# combined_pressure_sensor_rev0.net
KiCad netlist of a schematic drawn in EAGLE
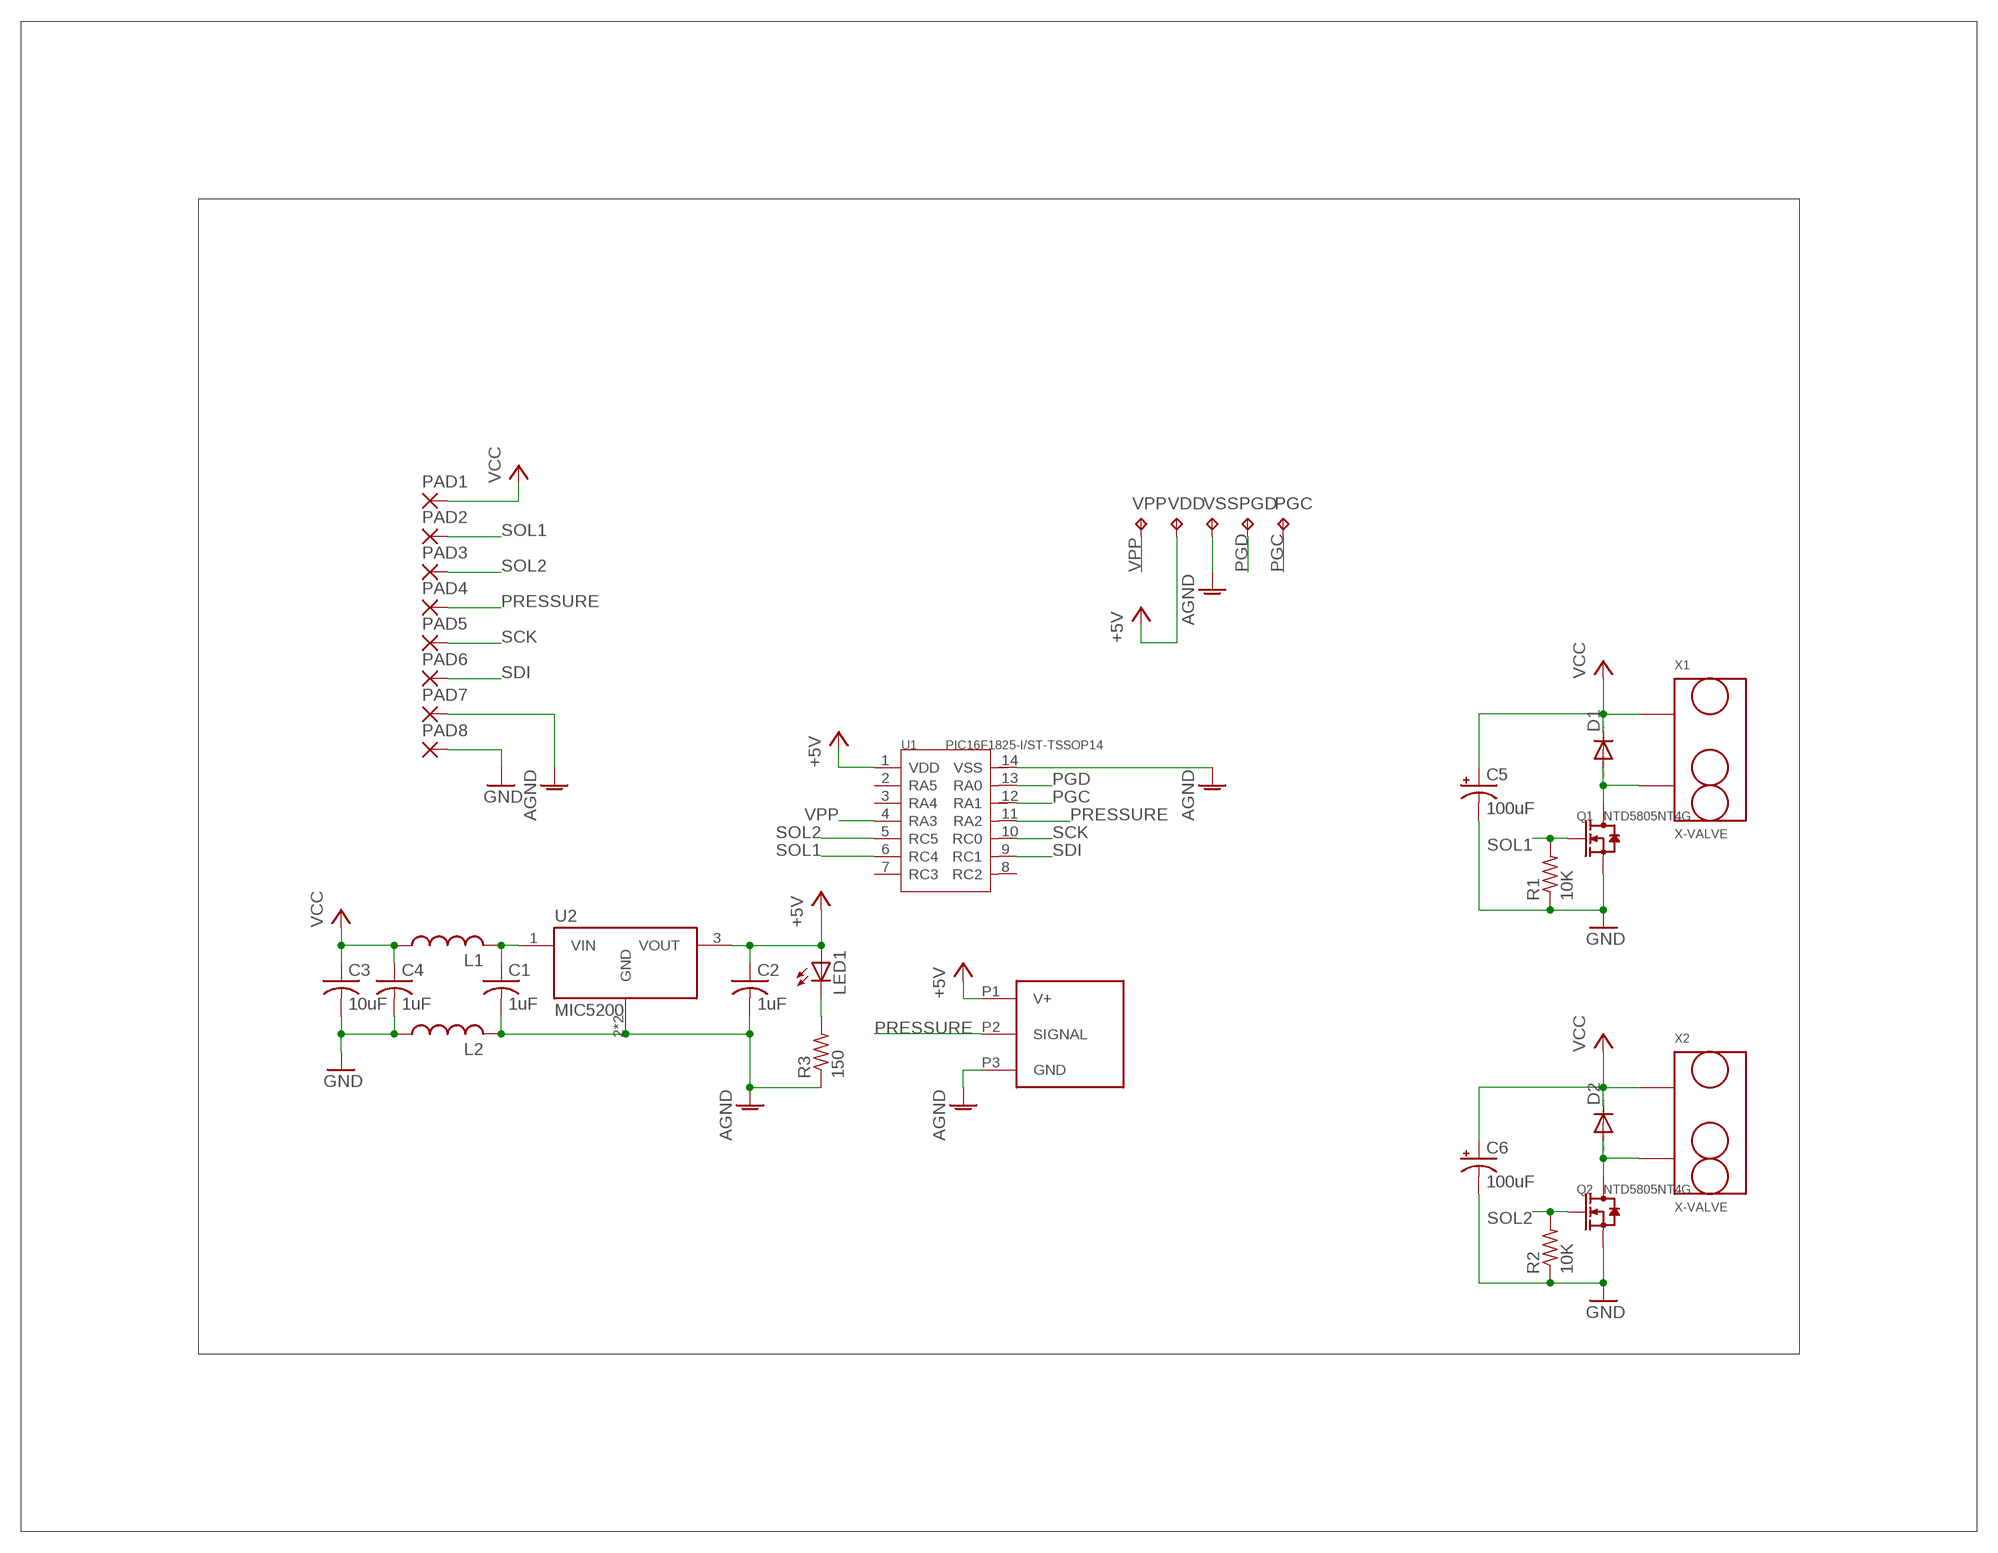
[diagram p0: schematic, sheet 1]

(export (version "E")
  (design (tool "Eeschema 10.0.6"))
  (components
    (comp (ref "C1")
      (value "1uF")
      (footprint "eagle-import:C0603")
      (libsource (lib "eagle-import") (part "C-USC0603"))
    )
    (comp (ref "C2")
      (value "1uF")
      (footprint "eagle-import:C0603")
      (libsource (lib "eagle-import") (part "C-USC0603"))
    )
    (comp (ref "C3")
      (value "10uF")
      (footprint "eagle-import:C1206")
      (libsource (lib "eagle-import") (part "C-USC1206"))
    )
    (comp (ref "C4")
      (value "1uF")
      (footprint "eagle-import:C0603")
      (libsource (lib "eagle-import") (part "C-USC0603"))
    )
    (comp (ref "C5")
      (value "100uF")
      (footprint "eagle-import:153CLV-0605")
      (libsource (lib "eagle-import") (part "CPOL-US153CLV-0605"))
    )
    (comp (ref "C6")
      (value "100uF")
      (footprint "eagle-import:153CLV-0605")
      (libsource (lib "eagle-import") (part "CPOL-US153CLV-0605"))
    )
    (comp (ref "D1")
      (value "DIODE-SOD523")
      (footprint "eagle-import:SOD523")
      (libsource (lib "eagle-import") (part "DIODE-SOD523"))
    )
    (comp (ref "D2")
      (value "DIODE-SOD523")
      (footprint "eagle-import:SOD523")
      (libsource (lib "eagle-import") (part "DIODE-SOD523"))
    )
    (comp (ref "L1")
      (value "L-USL1206")
      (footprint "eagle-import:L1206")
      (libsource (lib "eagle-import") (part "L-USL1206"))
    )
    (comp (ref "L2")
      (value "L-USL1206")
      (footprint "eagle-import:L1206")
      (libsource (lib "eagle-import") (part "L-USL1206"))
    )
    (comp (ref "LED1")
      (value "LEDCHIP-LED0603")
      (footprint "eagle-import:CHIP-LED0603")
      (libsource (lib "eagle-import") (part "LEDCHIP-LED0603"))
    )
    (comp (ref "PAD1")
      (value "SMD2")
      (footprint "eagle-import:SMD1,27-2,54")
      (libsource (lib "eagle-import") (part "SMD2"))
    )
    (comp (ref "PAD2")
      (value "SMD2")
      (footprint "eagle-import:SMD1,27-2,54")
      (libsource (lib "eagle-import") (part "SMD2"))
    )
    (comp (ref "PAD3")
      (value "SMD2")
      (footprint "eagle-import:SMD1,27-2,54")
      (libsource (lib "eagle-import") (part "SMD2"))
    )
    (comp (ref "PAD4")
      (value "SMD2")
      (footprint "eagle-import:SMD1,27-2,54")
      (libsource (lib "eagle-import") (part "SMD2"))
    )
    (comp (ref "PAD5")
      (value "SMD2")
      (footprint "eagle-import:SMD1,27-2,54")
      (libsource (lib "eagle-import") (part "SMD2"))
    )
    (comp (ref "PAD6")
      (value "SMD2")
      (footprint "eagle-import:SMD1,27-2,54")
      (libsource (lib "eagle-import") (part "SMD2"))
    )
    (comp (ref "PAD7")
      (value "SMD2")
      (footprint "eagle-import:SMD1,27-2,54")
      (libsource (lib "eagle-import") (part "SMD2"))
    )
    (comp (ref "PAD8")
      (value "SMD2")
      (footprint "eagle-import:SMD1,27-2,54")
      (libsource (lib "eagle-import") (part "SMD2"))
    )
    (comp (ref "PGC")
      (value "TPB1,27")
      (footprint "eagle-import:B1,27")
      (libsource (lib "eagle-import") (part "TPB1,27"))
    )
    (comp (ref "PGD")
      (value "TPB1,27")
      (footprint "eagle-import:B1,27")
      (libsource (lib "eagle-import") (part "TPB1,27"))
    )
    (comp (ref "Q1")
      (value "NTD5805NT4G")
      (footprint "eagle-import:DPAK")
      (libsource (lib "eagle-import") (part "SMD-MOSFET-HIGH-POWER-N-CH-40V-51A-NTD5805NT4G(DPAK)"))
    )
    (comp (ref "Q2")
      (value "NTD5805NT4G")
      (footprint "eagle-import:DPAK")
      (libsource (lib "eagle-import") (part "SMD-MOSFET-HIGH-POWER-N-CH-40V-51A-NTD5805NT4G(DPAK)"))
    )
    (comp (ref "R1")
      (value "10K")
      (footprint "eagle-import:R0603")
      (libsource (lib "eagle-import") (part "R-US_R0603"))
    )
    (comp (ref "R2")
      (value "10K")
      (footprint "eagle-import:R0603")
      (libsource (lib "eagle-import") (part "R-US_R0603"))
    )
    (comp (ref "R3")
      (value "150")
      (footprint "eagle-import:R0603")
      (libsource (lib "eagle-import") (part "R-US_R0603"))
    )
    (comp (ref "U$3")
      (value "ASDX")
      (footprint "eagle-import:ASDX")
      (libsource (lib "eagle-import") (part "ASDX"))
    )
    (comp (ref "U1")
      (value "PIC16F1825-I/ST-TSSOP14")
      (footprint "eagle-import:TSSOP14-0.65-5X4.4MM")
      (fields (field (name "MPN") "PIC16F1825-I/ST"))
      (libsource (lib "eagle-import") (part "MCU-PIC16F1825-I/ST(TSSOP14)"))
    )
    (comp (ref "U2")
      (value "MIC5200")
      (footprint "eagle-import:SOT223")
      (libsource (lib "eagle-import") (part "MIC5200"))
    )
    (comp (ref "VDD")
      (value "TPB1,27")
      (footprint "eagle-import:B1,27")
      (libsource (lib "eagle-import") (part "TPB1,27"))
    )
    (comp (ref "VPP")
      (value "TPB1,27")
      (footprint "eagle-import:B1,27")
      (libsource (lib "eagle-import") (part "TPB1,27"))
    )
    (comp (ref "VSS")
      (value "TPB1,27")
      (footprint "eagle-import:B1,27")
      (libsource (lib "eagle-import") (part "TPB1,27"))
    )
    (comp (ref "X1")
      (value "X-VALVE")
      (footprint "eagle-import:X-VALVE")
      (libsource (lib "eagle-import") (part "X-VALVE"))
    )
    (comp (ref "X2")
      (value "X-VALVE")
      (footprint "eagle-import:X-VALVE")
      (libsource (lib "eagle-import") (part "X-VALVE"))
    )
  )
  (nets
    (net (code "1") (name "+5V") (class "Default")
      (node (ref "C2") (pin "1") (pinfunction "1_1") (pintype "passive"))
      (node (ref "LED1") (pin "A") (pinfunction "A_A") (pintype "passive"))
      (node (ref "U$3") (pin "P1") (pinfunction "V+_P1") (pintype "bidirectional"))
      (node (ref "U1") (pin "1") (pinfunction "VDD_1") (pintype "bidirectional"))
      (node (ref "U2") (pin "3") (pinfunction "VOUT_3") (pintype "bidirectional"))
      (node (ref "VDD") (pin "TP") (pinfunction "TP_TP") (pintype "input"))
    )
    (net (code "2") (name "/PGC") (class "Default")
      (node (ref "PGC") (pin "TP") (pinfunction "TP_TP") (pintype "input"))
      (node (ref "U1") (pin "12") (pinfunction "RA1_12") (pintype "bidirectional"))
    )
    (net (code "3") (name "/PGD") (class "Default")
      (node (ref "PGD") (pin "TP") (pinfunction "TP_TP") (pintype "input"))
      (node (ref "U1") (pin "13") (pinfunction "RA0_13") (pintype "bidirectional"))
    )
    (net (code "4") (name "/PRESSURE") (class "Default")
      (node (ref "PAD4") (pin "1") (pinfunction "P_1") (pintype "passive"))
      (node (ref "U$3") (pin "P2") (pinfunction "SIGNAL_P2") (pintype "bidirectional"))
      (node (ref "U1") (pin "11") (pinfunction "RA2_11") (pintype "bidirectional"))
    )
    (net (code "5") (name "/SCK") (class "Default")
      (node (ref "PAD5") (pin "1") (pinfunction "P_1") (pintype "passive"))
      (node (ref "U1") (pin "10") (pinfunction "RC0_10") (pintype "bidirectional"))
    )
    (net (code "6") (name "/SDI") (class "Default")
      (node (ref "PAD6") (pin "1") (pinfunction "P_1") (pintype "passive"))
      (node (ref "U1") (pin "9") (pinfunction "RC1_9") (pintype "bidirectional"))
    )
    (net (code "7") (name "/SOL1") (class "Default")
      (node (ref "PAD2") (pin "1") (pinfunction "P_1") (pintype "passive"))
      (node (ref "Q1") (pin "1") (pinfunction "G_1") (pintype "passive"))
      (node (ref "R1") (pin "2") (pinfunction "2_2") (pintype "passive"))
      (node (ref "U1") (pin "6") (pinfunction "RC4_6") (pintype "bidirectional"))
    )
    (net (code "8") (name "/SOL2") (class "Default")
      (node (ref "PAD3") (pin "1") (pinfunction "P_1") (pintype "passive"))
      (node (ref "Q2") (pin "1") (pinfunction "G_1") (pintype "passive"))
      (node (ref "R2") (pin "2") (pinfunction "2_2") (pintype "passive"))
      (node (ref "U1") (pin "5") (pinfunction "RC5_5") (pintype "bidirectional"))
    )
    (net (code "9") (name "/VPP") (class "Default")
      (node (ref "U1") (pin "4") (pinfunction "RA3_4") (pintype "bidirectional"))
      (node (ref "VPP") (pin "TP") (pinfunction "TP_TP") (pintype "input"))
    )
    (net (code "10") (name "AGND") (class "Default")
      (node (ref "C1") (pin "2") (pinfunction "2_2") (pintype "passive"))
      (node (ref "C2") (pin "2") (pinfunction "2_2") (pintype "passive"))
      (node (ref "L2") (pin "2") (pinfunction "2_2") (pintype "passive"))
      (node (ref "PAD7") (pin "1") (pinfunction "P_1") (pintype "passive"))
      (node (ref "R3") (pin "1") (pinfunction "1_1") (pintype "passive"))
      (node (ref "U$3") (pin "P3") (pinfunction "GND_P3") (pintype "bidirectional"))
      (node (ref "U1") (pin "14") (pinfunction "VSS_14") (pintype "bidirectional"))
      (node (ref "U2") (pin "2") (pinfunction "GND_2") (pintype "bidirectional"))
      (node (ref "U2") (pin "4") (pinfunction "GND_4") (pintype "bidirectional"))
      (node (ref "VSS") (pin "TP") (pinfunction "TP_TP") (pintype "input"))
    )
    (net (code "11") (name "GND") (class "Default")
      (node (ref "C3") (pin "2") (pinfunction "2_2") (pintype "passive"))
      (node (ref "C4") (pin "2") (pinfunction "2_2") (pintype "passive"))
      (node (ref "C5") (pin "-") (pinfunction "-_-") (pintype "passive"))
      (node (ref "C6") (pin "-") (pinfunction "-_-") (pintype "passive"))
      (node (ref "L2") (pin "1") (pinfunction "1_1") (pintype "passive"))
      (node (ref "PAD8") (pin "1") (pinfunction "P_1") (pintype "passive"))
      (node (ref "Q1") (pin "2") (pinfunction "S_2") (pintype "passive"))
      (node (ref "Q2") (pin "2") (pinfunction "S_2") (pintype "passive"))
      (node (ref "R1") (pin "1") (pinfunction "1_1") (pintype "passive"))
      (node (ref "R2") (pin "1") (pinfunction "1_1") (pintype "passive"))
    )
    (net (code "12") (name "Net-(LED1-PadC)") (class "Default")
      (node (ref "LED1") (pin "C") (pinfunction "C_C") (pintype "passive"))
      (node (ref "R3") (pin "2") (pinfunction "2_2") (pintype "passive"))
    )
    (net (code "13") (name "Net-(Q1-D)") (class "Default")
      (node (ref "D1") (pin "A") (pinfunction "A_A") (pintype "passive"))
      (node (ref "Q1") (pin "3") (pinfunction "D_3") (pintype "passive"))
      (node (ref "X1") (pin "P$2") (pinfunction "P$2_P$2") (pintype "bidirectional"))
    )
    (net (code "14") (name "Net-(Q2-D)") (class "Default")
      (node (ref "D2") (pin "A") (pinfunction "A_A") (pintype "passive"))
      (node (ref "Q2") (pin "3") (pinfunction "D_3") (pintype "passive"))
      (node (ref "X2") (pin "P$2") (pinfunction "P$2_P$2") (pintype "bidirectional"))
    )
    (net (code "15") (name "Net-(U2-VIN)") (class "Default")
      (node (ref "C1") (pin "1") (pinfunction "1_1") (pintype "passive"))
      (node (ref "L1") (pin "2") (pinfunction "2_2") (pintype "passive"))
      (node (ref "U2") (pin "1") (pinfunction "VIN_1") (pintype "bidirectional"))
    )
    (net (code "16") (name "VCC") (class "Default")
      (node (ref "C3") (pin "1") (pinfunction "1_1") (pintype "passive"))
      (node (ref "C4") (pin "1") (pinfunction "1_1") (pintype "passive"))
      (node (ref "C5") (pin "+") (pinfunction "+_+") (pintype "passive"))
      (node (ref "C6") (pin "+") (pinfunction "+_+") (pintype "passive"))
      (node (ref "D1") (pin "C") (pinfunction "C_C") (pintype "passive"))
      (node (ref "D2") (pin "C") (pinfunction "C_C") (pintype "passive"))
      (node (ref "L1") (pin "1") (pinfunction "1_1") (pintype "passive"))
      (node (ref "PAD1") (pin "1") (pinfunction "P_1") (pintype "passive"))
      (node (ref "X1") (pin "P$1") (pinfunction "P$1_P$1") (pintype "bidirectional"))
      (node (ref "X2") (pin "P$1") (pinfunction "P$1_P$1") (pintype "bidirectional"))
    )
    (net (code "17") (name "unconnected-(U1-RA4-Pad3)") (class "Default")
      (node (ref "U1") (pin "3") (pinfunction "RA4_3") (pintype "bidirectional"))
    )
    (net (code "18") (name "unconnected-(U1-RA5-Pad2)") (class "Default")
      (node (ref "U1") (pin "2") (pinfunction "RA5_2") (pintype "bidirectional"))
    )
    (net (code "19") (name "unconnected-(U1-RC2-Pad8)") (class "Default")
      (node (ref "U1") (pin "8") (pinfunction "RC2_8") (pintype "bidirectional"))
    )
    (net (code "20") (name "unconnected-(U1-RC3-Pad7)") (class "Default")
      (node (ref "U1") (pin "7") (pinfunction "RC3_7") (pintype "bidirectional"))
    )
  )
)
